# DA2_SCH_PAGE2.net
KiCad netlist of a schematic drawn in Altium Designer
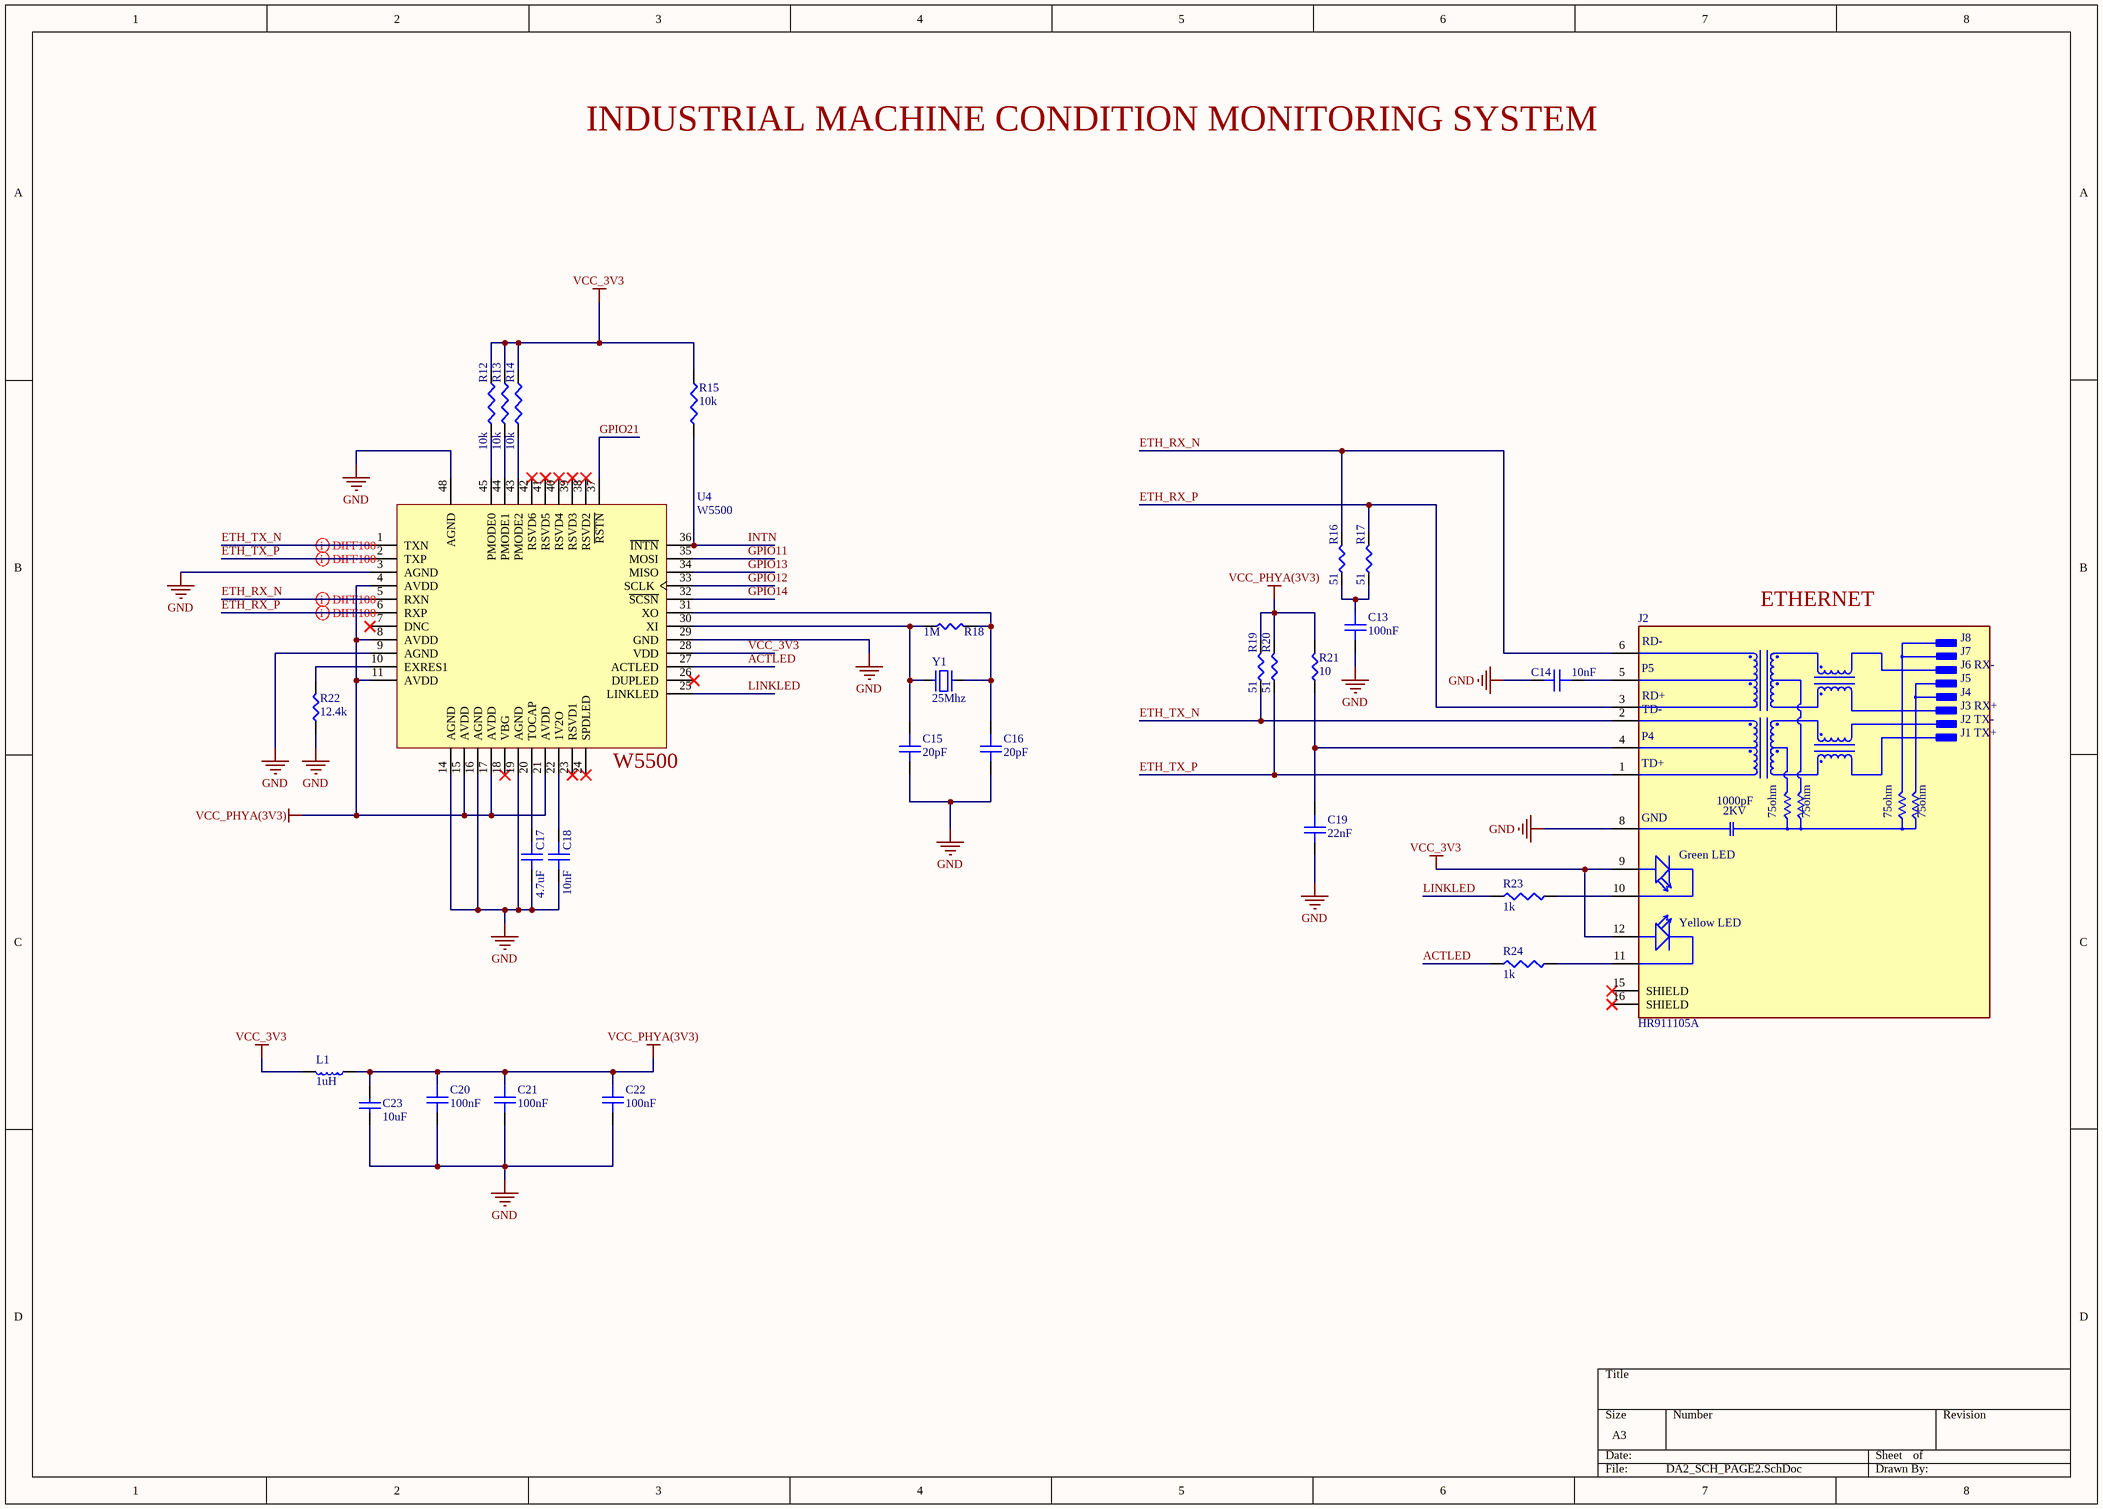
[diagram p0: DA2_SCH_PAGE2.SchDoc]

(export (version "E")
  (design (tool "Eeschema 10.0.6"))
  (components
    (comp (ref "C13")
      (value "100nF")
      (footprint "tu 0805")
      (description "Dán 0805")
      (libsource (lib "DA2") (part "Tu 100nF"))
    )
    (comp (ref "C14")
      (value "10nF")
      (footprint "tu 0805")
      (description "Dán 0805")
      (libsource (lib "DA2") (part "Tu 10nF"))
    )
    (comp (ref "C15")
      (value "20pF")
      (footprint "tu 0805")
      (description "Dán 0805")
      (libsource (lib "DA2") (part "Tu  20pF"))
    )
    (comp (ref "C16")
      (value "20pF")
      (footprint "tu 0805")
      (description "Dán 0805")
      (libsource (lib "DA2") (part "Tu  20pF"))
    )
    (comp (ref "C17")
      (value "4.7uF")
      (footprint "Tu 0805")
      (description "Dán 0805")
      (libsource (lib "DA2") (part "Tu 4.7uF"))
    )
    (comp (ref "C18")
      (value "10nF")
      (footprint "tu 0805")
      (description "Dán 0805")
      (libsource (lib "DA2") (part "Tu 10nF"))
    )
    (comp (ref "C19")
      (value "22nF")
      (footprint "tu 0805")
      (description "Dán 0805")
      (libsource (lib "DA2") (part "Tu 22nF"))
    )
    (comp (ref "C20")
      (value "100nF")
      (footprint "tu 0805")
      (description "Dán 0805")
      (libsource (lib "DA2") (part "Tu 100nF"))
    )
    (comp (ref "C21")
      (value "100nF")
      (footprint "tu 0805")
      (description "Dán 0805")
      (libsource (lib "DA2") (part "Tu 100nF"))
    )
    (comp (ref "C22")
      (value "100nF")
      (footprint "tu 0805")
      (description "Dán 0805")
      (libsource (lib "DA2") (part "Tu 100nF"))
    )
    (comp (ref "C23")
      (value "10uF")
      (footprint "Tu 0805")
      (description "Dán 0805")
      (fields
        (field (name "MANUFACTURER") "Samsung Electro-Mechanics")
        (field (name "MANUFACTURER PART NUMBER") "CL05A106MP5NUNC")
      )
      (libsource (lib "DA2") (part "Tu 10uF"))
    )
    (comp (ref "J2")
      (value "HR911105A")
      (footprint "HANRUN_HR911105A")
      (description "DIP RJ45 Connector;")
      (fields (field (name "MF") "hanrun"))
      (libsource (lib "Schlib1") (part "HR911105A"))
    )
    (comp (ref "L1")
      (value "1uH")
      (footprint "Tu 0805")
      (description "Dán 0805")
      (libsource (lib "DA2") (part "Cuon Cam 1uH"))
    )
    (comp (ref "R12")
      (value "10k")
      (footprint "Tro SMD 0805")
      (description "Dán 0805")
      (fields
        (field (name "MANUFACTURER") "Yageo Group")
        (field (name "MANUFACTURER PART NUMBER") "RC0402FR-0710KL")
      )
      (libsource (lib "DA2") (part "Tro 10k"))
    )
    (comp (ref "R13")
      (value "10k")
      (footprint "Tro SMD 0805")
      (description "Dán 0805")
      (fields
        (field (name "MANUFACTURER") "Yageo Group")
        (field (name "MANUFACTURER PART NUMBER") "RC0402FR-0710KL")
      )
      (libsource (lib "DA2") (part "Tro 10k"))
    )
    (comp (ref "R14")
      (value "10k")
      (footprint "Tro SMD 0805")
      (description "Dán 0805")
      (fields
        (field (name "MANUFACTURER") "Yageo Group")
        (field (name "MANUFACTURER PART NUMBER") "RC0402FR-0710KL")
      )
      (libsource (lib "DA2") (part "Tro 10k"))
    )
    (comp (ref "R15")
      (value "10k")
      (footprint "Tro SMD 0805")
      (description "Dán 0805")
      (fields
        (field (name "MANUFACTURER") "Yageo Group")
        (field (name "MANUFACTURER PART NUMBER") "RC0402FR-0710KL")
      )
      (libsource (lib "DA2") (part "Tro 10k"))
    )
    (comp (ref "R16")
      (value "51")
      (footprint "tro smd 0805")
      (description "Dán 0805")
      (libsource (lib "DA2") (part "Tro 51"))
    )
    (comp (ref "R17")
      (value "51")
      (footprint "tro smd 0805")
      (description "Dán 0805")
      (libsource (lib "DA2") (part "Tro 51"))
    )
    (comp (ref "R18")
      (value "1M")
      (footprint "tro smd 0805")
      (description "Dán 0805")
      (libsource (lib "DA2") (part "Tro 1M"))
    )
    (comp (ref "R19")
      (value "51")
      (footprint "tro smd 0805")
      (description "Dán 0805")
      (libsource (lib "DA2") (part "Tro 51"))
    )
    (comp (ref "R20")
      (value "51")
      (footprint "tro smd 0805")
      (description "Dán 0805")
      (libsource (lib "DA2") (part "Tro 51"))
    )
    (comp (ref "R21")
      (value "10")
      (footprint "tro smd 0805")
      (description "Dán 0805")
      (libsource (lib "DA2") (part "Tro 10"))
    )
    (comp (ref "R22")
      (value "12.4k")
      (footprint "tro smd 0805")
      (description "Dán 0805")
      (libsource (lib "DA2") (part "Tro 12.4k"))
    )
    (comp (ref "R23")
      (value "1k")
      (footprint "Tro SMD 0805")
      (description "Dán 0805")
      (fields
        (field (name "MANUFACTURER") "Yageo Group")
        (field (name "MANUFACTURER PART NUMBER") "RC0402JR-071KL")
      )
      (libsource (lib "DA2") (part "Tro 1k"))
    )
    (comp (ref "R24")
      (value "1k")
      (footprint "Tro SMD 0805")
      (description "Dán 0805")
      (fields
        (field (name "MANUFACTURER") "Yageo Group")
        (field (name "MANUFACTURER PART NUMBER") "RC0402JR-071KL")
      )
      (libsource (lib "DA2") (part "Tro 1k"))
    )
    (comp (ref "U4")
      (value "W5500")
      (footprint "QFP50P900X900X160-48N")
      (description "Hardwired TCP/IP embedded Ethernet controller")
      (libsource (lib "Schlib1") (part "W5500"))
    )
    (comp (ref "Y1")
      (value "25Mhz")
      (footprint "XTAL 25.000MHz")
      (description "Crystal For all Crystal 2pin.")
      (libsource (lib "DA2") (part "Thach Anh 2 chan SMD 5032"))
    )
  )
  (nets
    (net (code "1") (name "/ACTLED") (class "Default")
      (node (ref "R24") (pin "1") (pinfunction "1_1") (pintype "passive"))
      (node (ref "U4") (pin "27") (pinfunction "ACTLED_27") (pintype "passive"))
    )
    (net (code "2") (name "/ETH_RX_N") (class "Default")
      (node (ref "J2") (pin "6") (pinfunction "RD-_6") (pintype "passive"))
      (node (ref "R16") (pin "2") (pinfunction "2_2") (pintype "passive"))
      (node (ref "U4") (pin "5") (pinfunction "RXN_5") (pintype "passive"))
    )
    (net (code "3") (name "/ETH_RX_P") (class "Default")
      (node (ref "J2") (pin "3") (pinfunction "RD+_3") (pintype "passive"))
      (node (ref "R17") (pin "2") (pinfunction "2_2") (pintype "passive"))
      (node (ref "U4") (pin "6") (pinfunction "RXP_6") (pintype "passive"))
    )
    (net (code "4") (name "/ETH_TX_N") (class "Default")
      (node (ref "J2") (pin "2") (pinfunction "TD-_2") (pintype "passive"))
      (node (ref "R19") (pin "1") (pinfunction "1_1") (pintype "passive"))
      (node (ref "U4") (pin "1") (pinfunction "TXN_1") (pintype "passive"))
    )
    (net (code "5") (name "/ETH_TX_P") (class "Default")
      (node (ref "J2") (pin "1") (pinfunction "TD+_1") (pintype "passive"))
      (node (ref "R20") (pin "1") (pinfunction "1_1") (pintype "passive"))
      (node (ref "U4") (pin "2") (pinfunction "TXP_2") (pintype "passive"))
    )
    (net (code "6") (name "/GPIO11") (class "Default")
      (node (ref "U4") (pin "35") (pinfunction "MOSI_35") (pintype "passive"))
    )
    (net (code "7") (name "/GPIO12") (class "Default")
      (node (ref "U4") (pin "33") (pinfunction "SCLK_33") (pintype "passive"))
    )
    (net (code "8") (name "/GPIO13") (class "Default")
      (node (ref "U4") (pin "34") (pinfunction "MISO_34") (pintype "passive"))
    )
    (net (code "9") (name "/GPIO14") (class "Default")
      (node (ref "U4") (pin "32") (pinfunction "~{SCSN}_32") (pintype "passive"))
    )
    (net (code "10") (name "/GPIO21") (class "Default")
      (node (ref "U4") (pin "37") (pinfunction "~{RSTN}_37") (pintype "passive"))
    )
    (net (code "11") (name "/INTN") (class "Default")
      (node (ref "R15") (pin "1") (pinfunction "1_1") (pintype "passive"))
      (node (ref "U4") (pin "36") (pinfunction "~{INTN}_36") (pintype "passive"))
    )
    (net (code "12") (name "/LINKLED") (class "Default")
      (node (ref "R23") (pin "1") (pinfunction "1_1") (pintype "passive"))
      (node (ref "U4") (pin "25") (pinfunction "LINKLED_25") (pintype "passive"))
    )
    (net (code "13") (name "GND") (class "Default")
      (node (ref "C13") (pin "2") (pinfunction "2_2") (pintype "passive"))
      (node (ref "C14") (pin "2") (pinfunction "2_2") (pintype "passive"))
      (node (ref "C15") (pin "2") (pinfunction "2_2") (pintype "passive"))
      (node (ref "C16") (pin "2") (pinfunction "2_2") (pintype "passive"))
      (node (ref "C17") (pin "2") (pinfunction "2_2") (pintype "passive"))
      (node (ref "C18") (pin "2") (pinfunction "2_2") (pintype "passive"))
      (node (ref "C19") (pin "2") (pinfunction "2_2") (pintype "passive"))
      (node (ref "C20") (pin "2") (pinfunction "2_2") (pintype "passive"))
      (node (ref "C21") (pin "2") (pinfunction "2_2") (pintype "passive"))
      (node (ref "C22") (pin "2") (pinfunction "2_2") (pintype "passive"))
      (node (ref "C23") (pin "1") (pinfunction "1_1") (pintype "passive"))
      (node (ref "J2") (pin "8") (pinfunction "GND_8") (pintype "power_in"))
      (node (ref "R22") (pin "1") (pinfunction "1_1") (pintype "passive"))
      (node (ref "U4") (pin "14") (pinfunction "AGND_14") (pintype "passive"))
      (node (ref "U4") (pin "16") (pinfunction "AGND_16") (pintype "passive"))
      (node (ref "U4") (pin "19") (pinfunction "AGND_19") (pintype "passive"))
      (node (ref "U4") (pin "29") (pinfunction "GND_29") (pintype "passive"))
      (node (ref "U4") (pin "3") (pinfunction "AGND_3") (pintype "passive"))
      (node (ref "U4") (pin "48") (pinfunction "AGND_48") (pintype "passive"))
      (node (ref "U4") (pin "9") (pinfunction "AGND_9") (pintype "passive"))
    )
    (net (code "14") (name "Net-(C13-Pad1)") (class "Default")
      (node (ref "C13") (pin "1") (pinfunction "1_1") (pintype "passive"))
      (node (ref "R16") (pin "1") (pinfunction "1_1") (pintype "passive"))
      (node (ref "R17") (pin "1") (pinfunction "1_1") (pintype "passive"))
    )
    (net (code "15") (name "Net-(J2-GC)") (class "Default")
      (node (ref "J2") (pin "10") (pinfunction "GC_10") (pintype "passive"))
      (node (ref "R23") (pin "2") (pinfunction "2_2") (pintype "passive"))
    )
    (net (code "16") (name "Net-(J2-P4)") (class "Default")
      (node (ref "C19") (pin "1") (pinfunction "1_1") (pintype "passive"))
      (node (ref "J2") (pin "4") (pinfunction "P4_4") (pintype "passive"))
      (node (ref "R21") (pin "1") (pinfunction "1_1") (pintype "passive"))
    )
    (net (code "17") (name "Net-(J2-P5)") (class "Default")
      (node (ref "C14") (pin "1") (pinfunction "1_1") (pintype "passive"))
      (node (ref "J2") (pin "5") (pinfunction "P5_5") (pintype "passive"))
    )
    (net (code "18") (name "Net-(J2-YC)") (class "Default")
      (node (ref "J2") (pin "11") (pinfunction "YC_11") (pintype "passive"))
      (node (ref "R24") (pin "2") (pinfunction "2_2") (pintype "passive"))
    )
    (net (code "19") (name "Net-(U4-1V2O)") (class "Default")
      (node (ref "C18") (pin "1") (pinfunction "1_1") (pintype "passive"))
      (node (ref "U4") (pin "22") (pinfunction "1V2O_22") (pintype "passive"))
    )
    (net (code "20") (name "Net-(U4-EXRES1)") (class "Default")
      (node (ref "R22") (pin "2") (pinfunction "2_2") (pintype "passive"))
      (node (ref "U4") (pin "10") (pinfunction "EXRES1_10") (pintype "passive"))
    )
    (net (code "21") (name "Net-(U4-PMODE0)") (class "Default")
      (node (ref "R12") (pin "1") (pinfunction "1_1") (pintype "passive"))
      (node (ref "U4") (pin "45") (pinfunction "PMODE0_45") (pintype "passive"))
    )
    (net (code "22") (name "Net-(U4-PMODE1)") (class "Default")
      (node (ref "R13") (pin "1") (pinfunction "1_1") (pintype "passive"))
      (node (ref "U4") (pin "44") (pinfunction "PMODE1_44") (pintype "passive"))
    )
    (net (code "23") (name "Net-(U4-PMODE2)") (class "Default")
      (node (ref "R14") (pin "1") (pinfunction "1_1") (pintype "passive"))
      (node (ref "U4") (pin "43") (pinfunction "PMODE2_43") (pintype "passive"))
    )
    (net (code "24") (name "Net-(U4-TOCAP)") (class "Default")
      (node (ref "C17") (pin "1") (pinfunction "1_1") (pintype "passive"))
      (node (ref "U4") (pin "20") (pinfunction "TOCAP_20") (pintype "passive"))
    )
    (net (code "25") (name "Net-(U4-XI)") (class "Default")
      (node (ref "C15") (pin "1") (pinfunction "1_1") (pintype "passive"))
      (node (ref "R18") (pin "1") (pinfunction "1_1") (pintype "passive"))
      (node (ref "U4") (pin "30") (pinfunction "XI_30") (pintype "passive"))
      (node (ref "Y1") (pin "1") (pinfunction "1_1") (pintype "passive"))
    )
    (net (code "26") (name "Net-(U4-XO)") (class "Default")
      (node (ref "C16") (pin "1") (pinfunction "1_1") (pintype "passive"))
      (node (ref "R18") (pin "2") (pinfunction "2_2") (pintype "passive"))
      (node (ref "U4") (pin "31") (pinfunction "XO_31") (pintype "passive"))
      (node (ref "Y1") (pin "2") (pinfunction "2_2") (pintype "passive"))
    )
    (net (code "27") (name "VCC_3V3") (class "Default")
      (node (ref "J2") (pin "12") (pinfunction "YA_12") (pintype "passive"))
      (node (ref "J2") (pin "9") (pinfunction "GA_9") (pintype "passive"))
      (node (ref "L1") (pin "1") (pinfunction "1_1") (pintype "passive"))
      (node (ref "R12") (pin "2") (pinfunction "2_2") (pintype "passive"))
      (node (ref "R13") (pin "2") (pinfunction "2_2") (pintype "passive"))
      (node (ref "R14") (pin "2") (pinfunction "2_2") (pintype "passive"))
      (node (ref "R15") (pin "2") (pinfunction "2_2") (pintype "passive"))
      (node (ref "U4") (pin "28") (pinfunction "VDD_28") (pintype "passive"))
    )
    (net (code "28") (name "VCC_PHYA(3V3)") (class "Default")
      (node (ref "C20") (pin "1") (pinfunction "1_1") (pintype "passive"))
      (node (ref "C21") (pin "1") (pinfunction "1_1") (pintype "passive"))
      (node (ref "C22") (pin "1") (pinfunction "1_1") (pintype "passive"))
      (node (ref "C23") (pin "2") (pinfunction "2_2") (pintype "passive"))
      (node (ref "L1") (pin "2") (pinfunction "2_2") (pintype "passive"))
      (node (ref "R19") (pin "2") (pinfunction "2_2") (pintype "passive"))
      (node (ref "R20") (pin "2") (pinfunction "2_2") (pintype "passive"))
      (node (ref "R21") (pin "2") (pinfunction "2_2") (pintype "passive"))
      (node (ref "U4") (pin "11") (pinfunction "AVDD_11") (pintype "passive"))
      (node (ref "U4") (pin "15") (pinfunction "AVDD_15") (pintype "passive"))
      (node (ref "U4") (pin "17") (pinfunction "AVDD_17") (pintype "passive"))
      (node (ref "U4") (pin "21") (pinfunction "AVDD_21") (pintype "passive"))
      (node (ref "U4") (pin "4") (pinfunction "AVDD_4") (pintype "passive"))
      (node (ref "U4") (pin "8") (pinfunction "AVDD_8") (pintype "passive"))
    )
    (net (code "29") (name "unconnected-(J2-SHIELD-Pad15)") (class "Default")
      (node (ref "J2") (pin "15") (pinfunction "SHIELD_15") (pintype "passive+no_connect"))
    )
    (net (code "30") (name "unconnected-(J2-SHIELD-Pad16)") (class "Default")
      (node (ref "J2") (pin "16") (pinfunction "SHIELD_16") (pintype "passive+no_connect"))
    )
    (net (code "31") (name "unconnected-(U4-DNC-Pad7)") (class "Default")
      (node (ref "U4") (pin "7") (pinfunction "DNC_7") (pintype "passive+no_connect"))
    )
    (net (code "32") (name "unconnected-(U4-DUPLED-Pad26)") (class "Default")
      (node (ref "U4") (pin "26") (pinfunction "DUPLED_26") (pintype "passive+no_connect"))
    )
    (net (code "33") (name "unconnected-(U4-RSVD1-Pad23)") (class "Default")
      (node (ref "U4") (pin "23") (pinfunction "RSVD1_23") (pintype "passive+no_connect"))
    )
    (net (code "34") (name "unconnected-(U4-RSVD2-Pad38)") (class "Default")
      (node (ref "U4") (pin "38") (pinfunction "RSVD2_38") (pintype "passive+no_connect"))
    )
    (net (code "35") (name "unconnected-(U4-RSVD3-Pad39)") (class "Default")
      (node (ref "U4") (pin "39") (pinfunction "RSVD3_39") (pintype "passive+no_connect"))
    )
    (net (code "36") (name "unconnected-(U4-RSVD4-Pad40)") (class "Default")
      (node (ref "U4") (pin "40") (pinfunction "RSVD4_40") (pintype "passive+no_connect"))
    )
    (net (code "37") (name "unconnected-(U4-RSVD5-Pad41)") (class "Default")
      (node (ref "U4") (pin "41") (pinfunction "RSVD5_41") (pintype "passive+no_connect"))
    )
    (net (code "38") (name "unconnected-(U4-RSVD6-Pad42)") (class "Default")
      (node (ref "U4") (pin "42") (pinfunction "RSVD6_42") (pintype "passive+no_connect"))
    )
    (net (code "39") (name "unconnected-(U4-SPDLED-Pad24)") (class "Default")
      (node (ref "U4") (pin "24") (pinfunction "SPDLED_24") (pintype "passive+no_connect"))
    )
    (net (code "40") (name "unconnected-(U4-VBG-Pad18)") (class "Default")
      (node (ref "U4") (pin "18") (pinfunction "VBG_18") (pintype "passive+no_connect"))
    )
  )
)
